# RF_SMA_WBC1-1.net
KiCad netlist of a schematic drawn in Altium Designer
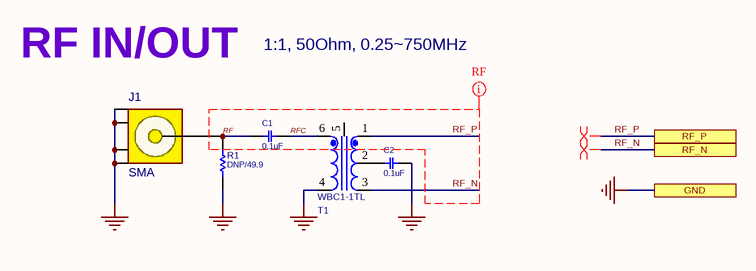
[diagram p0: RF_SMA_WBC1-1.SchDoc]

(export (version "E")
  (design (tool "Eeschema 10.0.6"))
  (components
    (comp (ref "C1")
      (value "0.1uF")
      (footprint "C0402")
      (description "CAP, MLCC")
      (fields (field (name "MANF_P#") "GRM155R61E104") (field (name "MANF") "Murata"))
      (libsource (lib "mlcc_smd_passive") (part "CAP_SMD_MLCC_100n50T"))
    )
    (comp (ref "C2")
      (value "0.1uF")
      (footprint "C0402")
      (description "CAP, MLCC")
      (fields (field (name "MANF_P#") "GRM155R61E104") (field (name "MANF") "Murata"))
      (libsource (lib "mlcc_smd_passive") (part "CAP_SMD_MLCC_100n50T"))
    )
    (comp (ref "J1")
      (value "SMA")
      (footprint "SMA_ST")
      (description "CONN, RF, SMA, STRAIGHT")
      (fields (field (name "MANF_P#") "142-0701-201") (field (name "MANF") "Johnson"))
      (libsource (lib "conn_rf") (part "CONN_RF_SMA_ST"))
    )
    (comp (ref "R1")
      (value "DNP/49.9")
      (footprint "R0402")
      (description "RESISTOR, SMD")
      (libsource (lib "passive_res_smd") (part "RES_SMD_10K_0402"))
    )
    (comp (ref "T1")
      (value "WBC1-1TL")
      (footprint "TRNS150_6_450X420")
      (description "RF Transformer, 1:1, 50Ohm, 0.25~750MHz")
      (fields (field (name "MANF") "Coilcraft"))
      (libsource (lib "transformer_rf") (part "WBC1-1TL"))
    )
  )
  (nets
    (net (code "1") (name "/RF") (class "Default")
      (node (ref "C1") (pin "1") (pinfunction "1_1") (pintype "passive"))
      (node (ref "J1") (pin "1") (pinfunction "SIG_1") (pintype "passive"))
      (node (ref "R1") (pin "2") (pinfunction "2_2") (pintype "passive"))
    )
    (net (code "2") (name "/RFC") (class "Default")
      (node (ref "C1") (pin "2") (pinfunction "2_2") (pintype "passive"))
      (node (ref "T1") (pin "6") (pinfunction "SECDOT_6") (pintype "passive"))
    )
    (net (code "3") (name "/RF_N") (class "Default")
      (node (ref "T1") (pin "3") (pinfunction "PRI_3") (pintype "passive"))
    )
    (net (code "4") (name "/RF_P") (class "Default")
      (node (ref "T1") (pin "1") (pinfunction "PRIDOT_1") (pintype "passive"))
    )
    (net (code "5") (name "GND") (class "Default")
      (node (ref "C2") (pin "2") (pinfunction "2_2") (pintype "passive"))
      (node (ref "J1") (pin "2") (pinfunction "G1_2") (pintype "passive"))
      (node (ref "J1") (pin "3") (pinfunction "G2_3") (pintype "passive"))
      (node (ref "J1") (pin "4") (pinfunction "G3_4") (pintype "passive"))
      (node (ref "J1") (pin "5") (pinfunction "G4_5") (pintype "passive"))
      (node (ref "R1") (pin "1") (pinfunction "1_1") (pintype "passive"))
      (node (ref "T1") (pin "4") (pinfunction "SEC_4") (pintype "passive"))
    )
    (net (code "6") (name "Net-(T1-PRICT)") (class "Default")
      (node (ref "C2") (pin "1") (pinfunction "1_1") (pintype "passive"))
      (node (ref "T1") (pin "2") (pinfunction "PRICT_2") (pintype "passive"))
    )
    (net (code "7") (name "unconnected-(T1-NC-Pad5)") (class "Default")
      (node (ref "T1") (pin "5") (pinfunction "NC_5") (pintype "passive"))
    )
  )
)
